# Protoboard_MX2-8-7-ESP12.net
KiCad netlist of a schematic drawn in EAGLE
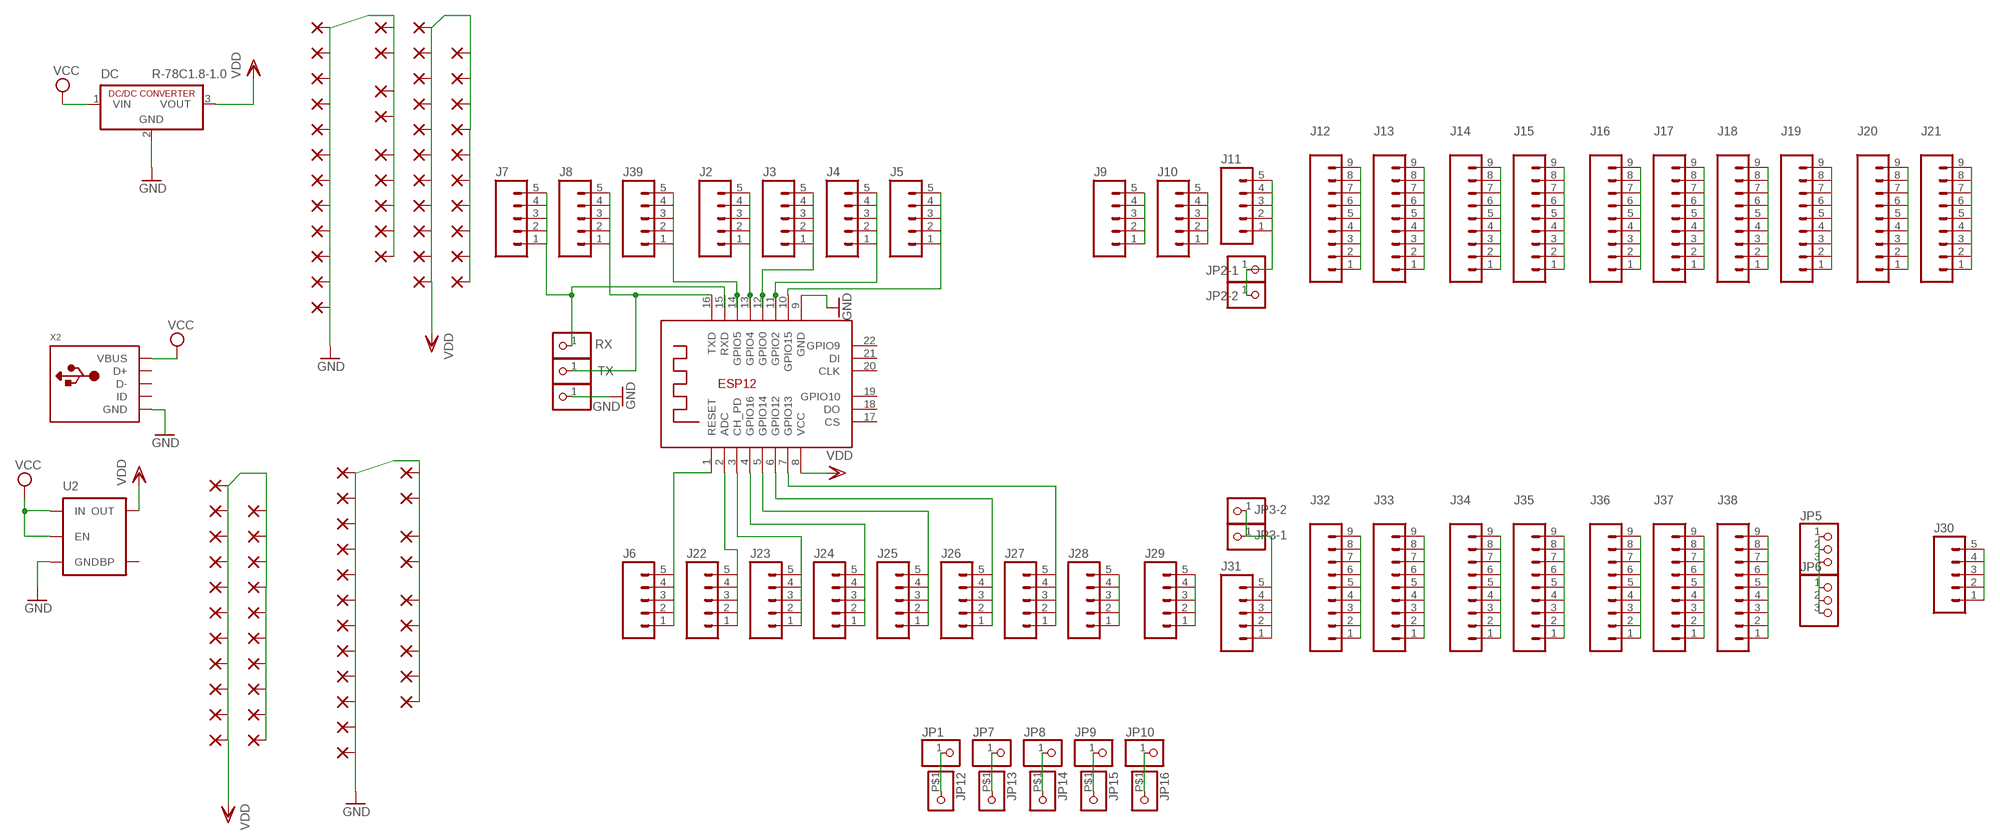
[diagram p0: schematic, sheet 1]

(export (version "E")
  (design (tool "Eeschema 10.0.6"))
  (components
    (comp (ref "DC")
      (value "R-78C1.8-1.0")
      (footprint "eagle-import:SIP3")
      (libsource (lib "eagle-import") (part "R-78C-1.01.8"))
    )
    (comp (ref "GND")
      (value "PINHD-1X1CB")
      (footprint "eagle-import:1X01-CLEANBIG")
      (libsource (lib "eagle-import") (part "PINHD-1X1CB"))
    )
    (comp (ref "J2")
      (value "M05NO_SILK")
      (footprint "eagle-import:1X05_NO_SILK")
      (libsource (lib "eagle-import") (part "M05NO_SILK"))
    )
    (comp (ref "J3")
      (value "M05NO_SILK")
      (footprint "eagle-import:1X05_NO_SILK")
      (libsource (lib "eagle-import") (part "M05NO_SILK"))
    )
    (comp (ref "J4")
      (value "M05NO_SILK")
      (footprint "eagle-import:1X05_NO_SILK")
      (libsource (lib "eagle-import") (part "M05NO_SILK"))
    )
    (comp (ref "J5")
      (value "M05NO_SILK")
      (footprint "eagle-import:1X05_NO_SILK")
      (libsource (lib "eagle-import") (part "M05NO_SILK"))
    )
    (comp (ref "J6")
      (value "M05NO_SILK")
      (footprint "eagle-import:1X05_NO_SILK")
      (libsource (lib "eagle-import") (part "M05NO_SILK"))
    )
    (comp (ref "J7")
      (value "M05NO_SILK")
      (footprint "eagle-import:1X05_NO_SILK")
      (libsource (lib "eagle-import") (part "M05NO_SILK"))
    )
    (comp (ref "J8")
      (value "M05NO_SILK")
      (footprint "eagle-import:1X05_NO_SILK")
      (libsource (lib "eagle-import") (part "M05NO_SILK"))
    )
    (comp (ref "J9")
      (value "M05NO_SILK")
      (footprint "eagle-import:1X05_NO_SILK")
      (libsource (lib "eagle-import") (part "M05NO_SILK"))
    )
    (comp (ref "J10")
      (value "M05NO_SILK")
      (footprint "eagle-import:1X05_NO_SILK")
      (libsource (lib "eagle-import") (part "M05NO_SILK"))
    )
    (comp (ref "J11")
      (value "M05NO_SILK")
      (footprint "eagle-import:1X05_NO_SILK")
      (libsource (lib "eagle-import") (part "M05NO_SILK"))
    )
    (comp (ref "J12")
      (value "M09NO_SILK")
      (footprint "eagle-import:1X09_NO_SILK")
      (libsource (lib "eagle-import") (part "M09NO_SILK"))
    )
    (comp (ref "J13")
      (value "M09NO_SILK")
      (footprint "eagle-import:1X09_NO_SILK")
      (libsource (lib "eagle-import") (part "M09NO_SILK"))
    )
    (comp (ref "J14")
      (value "M09NO_SILK")
      (footprint "eagle-import:1X09_NO_SILK")
      (libsource (lib "eagle-import") (part "M09NO_SILK"))
    )
    (comp (ref "J15")
      (value "M09NO_SILK")
      (footprint "eagle-import:1X09_NO_SILK")
      (libsource (lib "eagle-import") (part "M09NO_SILK"))
    )
    (comp (ref "J16")
      (value "M09NO_SILK")
      (footprint "eagle-import:1X09_NO_SILK")
      (libsource (lib "eagle-import") (part "M09NO_SILK"))
    )
    (comp (ref "J17")
      (value "M09NO_SILK")
      (footprint "eagle-import:1X09_NO_SILK")
      (libsource (lib "eagle-import") (part "M09NO_SILK"))
    )
    (comp (ref "J18")
      (value "M09NO_SILK")
      (footprint "eagle-import:1X09_NO_SILK")
      (libsource (lib "eagle-import") (part "M09NO_SILK"))
    )
    (comp (ref "J19")
      (value "M09NO_SILK")
      (footprint "eagle-import:1X09_NO_SILK")
      (libsource (lib "eagle-import") (part "M09NO_SILK"))
    )
    (comp (ref "J20")
      (value "M09NO_SILK")
      (footprint "eagle-import:1X09_NO_SILK")
      (libsource (lib "eagle-import") (part "M09NO_SILK"))
    )
    (comp (ref "J21")
      (value "M09NO_SILK")
      (footprint "eagle-import:1X09_NO_SILK")
      (libsource (lib "eagle-import") (part "M09NO_SILK"))
    )
    (comp (ref "J22")
      (value "M05NO_SILK")
      (footprint "eagle-import:1X05_NO_SILK")
      (libsource (lib "eagle-import") (part "M05NO_SILK"))
    )
    (comp (ref "J23")
      (value "M05NO_SILK")
      (footprint "eagle-import:1X05_NO_SILK")
      (libsource (lib "eagle-import") (part "M05NO_SILK"))
    )
    (comp (ref "J24")
      (value "M05NO_SILK")
      (footprint "eagle-import:1X05_NO_SILK")
      (libsource (lib "eagle-import") (part "M05NO_SILK"))
    )
    (comp (ref "J25")
      (value "M05NO_SILK")
      (footprint "eagle-import:1X05_NO_SILK")
      (libsource (lib "eagle-import") (part "M05NO_SILK"))
    )
    (comp (ref "J26")
      (value "M05NO_SILK")
      (footprint "eagle-import:1X05_NO_SILK")
      (libsource (lib "eagle-import") (part "M05NO_SILK"))
    )
    (comp (ref "J27")
      (value "M05NO_SILK")
      (footprint "eagle-import:1X05_NO_SILK")
      (libsource (lib "eagle-import") (part "M05NO_SILK"))
    )
    (comp (ref "J28")
      (value "M05NO_SILK")
      (footprint "eagle-import:1X05_NO_SILK")
      (libsource (lib "eagle-import") (part "M05NO_SILK"))
    )
    (comp (ref "J29")
      (value "M05NO_SILK")
      (footprint "eagle-import:1X05_NO_SILK")
      (libsource (lib "eagle-import") (part "M05NO_SILK"))
    )
    (comp (ref "J30")
      (value "M05NO_SILK")
      (footprint "eagle-import:1X05_NO_SILK")
      (libsource (lib "eagle-import") (part "M05NO_SILK"))
    )
    (comp (ref "J31")
      (value "M05NO_SILK")
      (footprint "eagle-import:1X05_NO_SILK")
      (libsource (lib "eagle-import") (part "M05NO_SILK"))
    )
    (comp (ref "J32")
      (value "M09NO_SILK")
      (footprint "eagle-import:1X09_NO_SILK")
      (libsource (lib "eagle-import") (part "M09NO_SILK"))
    )
    (comp (ref "J33")
      (value "M09NO_SILK")
      (footprint "eagle-import:1X09_NO_SILK")
      (libsource (lib "eagle-import") (part "M09NO_SILK"))
    )
    (comp (ref "J34")
      (value "M09NO_SILK")
      (footprint "eagle-import:1X09_NO_SILK")
      (libsource (lib "eagle-import") (part "M09NO_SILK"))
    )
    (comp (ref "J35")
      (value "M09NO_SILK")
      (footprint "eagle-import:1X09_NO_SILK")
      (libsource (lib "eagle-import") (part "M09NO_SILK"))
    )
    (comp (ref "J36")
      (value "M09NO_SILK")
      (footprint "eagle-import:1X09_NO_SILK")
      (libsource (lib "eagle-import") (part "M09NO_SILK"))
    )
    (comp (ref "J37")
      (value "M09NO_SILK")
      (footprint "eagle-import:1X09_NO_SILK")
      (libsource (lib "eagle-import") (part "M09NO_SILK"))
    )
    (comp (ref "J38")
      (value "M09NO_SILK")
      (footprint "eagle-import:1X09_NO_SILK")
      (libsource (lib "eagle-import") (part "M09NO_SILK"))
    )
    (comp (ref "J39")
      (value "M05NO_SILK")
      (footprint "eagle-import:1X05_NO_SILK")
      (libsource (lib "eagle-import") (part "M05NO_SILK"))
    )
    (comp (ref "JP1")
      (value "PINHD-1X1CB")
      (footprint "eagle-import:1X01-CLEANBIG")
      (libsource (lib "eagle-import") (part "PINHD-1X1CB"))
    )
    (comp (ref "JP2-1")
      (value "PINHD-1X1CB")
      (footprint "eagle-import:1X01-CLEANBIG")
      (libsource (lib "eagle-import") (part "PINHD-1X1CB"))
    )
    (comp (ref "JP2-2")
      (value "PINHD-1X1CB")
      (footprint "eagle-import:1X01-CLEANBIG")
      (libsource (lib "eagle-import") (part "PINHD-1X1CB"))
    )
    (comp (ref "JP3-1")
      (value "PINHD-1X1CB")
      (footprint "eagle-import:1X01-CLEANBIG")
      (libsource (lib "eagle-import") (part "PINHD-1X1CB"))
    )
    (comp (ref "JP3-2")
      (value "PINHD-1X1CB")
      (footprint "eagle-import:1X01-CLEANBIG")
      (libsource (lib "eagle-import") (part "PINHD-1X1CB"))
    )
    (comp (ref "JP5")
      (value "PINHD-1X3CB")
      (footprint "eagle-import:1X03-CLEANBIG")
      (libsource (lib "eagle-import") (part "PINHD-1X3CB"))
    )
    (comp (ref "JP6")
      (value "PINHD-1X3CB")
      (footprint "eagle-import:1X03-CLEANBIG")
      (libsource (lib "eagle-import") (part "PINHD-1X3CB"))
    )
    (comp (ref "JP7")
      (value "PINHD-1X1CB")
      (footprint "eagle-import:1X01-CLEANBIG")
      (libsource (lib "eagle-import") (part "PINHD-1X1CB"))
    )
    (comp (ref "JP8")
      (value "PINHD-1X1CB")
      (footprint "eagle-import:1X01-CLEANBIG")
      (libsource (lib "eagle-import") (part "PINHD-1X1CB"))
    )
    (comp (ref "JP9")
      (value "PINHD-1X1CB")
      (footprint "eagle-import:1X01-CLEANBIG")
      (libsource (lib "eagle-import") (part "PINHD-1X1CB"))
    )
    (comp (ref "JP10")
      (value "PINHD-1X1CB")
      (footprint "eagle-import:1X01-CLEANBIG")
      (libsource (lib "eagle-import") (part "PINHD-1X1CB"))
    )
    (comp (ref "JP12")
      (value "PINHD-1X1-BIGPOGO")
      (footprint "eagle-import:1X1-BIGPOGO")
      (libsource (lib "eagle-import") (part "PINHD-1X1-BIGPOGO"))
    )
    (comp (ref "JP13")
      (value "PINHD-1X1-BIGPOGO")
      (footprint "eagle-import:1X1-BIGPOGO")
      (libsource (lib "eagle-import") (part "PINHD-1X1-BIGPOGO"))
    )
    (comp (ref "JP14")
      (value "PINHD-1X1-BIGPOGO")
      (footprint "eagle-import:1X1-BIGPOGO")
      (libsource (lib "eagle-import") (part "PINHD-1X1-BIGPOGO"))
    )
    (comp (ref "JP15")
      (value "PINHD-1X1-BIGPOGO")
      (footprint "eagle-import:1X1-BIGPOGO")
      (libsource (lib "eagle-import") (part "PINHD-1X1-BIGPOGO"))
    )
    (comp (ref "JP16")
      (value "PINHD-1X1-BIGPOGO")
      (footprint "eagle-import:1X1-BIGPOGO")
      (libsource (lib "eagle-import") (part "PINHD-1X1-BIGPOGO"))
    )
    (comp (ref "PAD1")
      (value "1,6/0,8")
      (footprint "eagle-import:1,6_0,8")
      (libsource (lib "eagle-import") (part "1,6/0,8"))
    )
    (comp (ref "PAD2")
      (value "1,6/0,8")
      (footprint "eagle-import:1,6_0,8")
      (libsource (lib "eagle-import") (part "1,6/0,8"))
    )
    (comp (ref "PAD3")
      (value "1,6/0,8")
      (footprint "eagle-import:1,6_0,8")
      (libsource (lib "eagle-import") (part "1,6/0,8"))
    )
    (comp (ref "PAD4")
      (value "1,6/0,8")
      (footprint "eagle-import:1,6_0,8")
      (libsource (lib "eagle-import") (part "1,6/0,8"))
    )
    (comp (ref "PAD5")
      (value "1,6/0,8")
      (footprint "eagle-import:1,6_0,8")
      (libsource (lib "eagle-import") (part "1,6/0,8"))
    )
    (comp (ref "PAD6")
      (value "1,6/0,8")
      (footprint "eagle-import:1,6_0,8")
      (libsource (lib "eagle-import") (part "1,6/0,8"))
    )
    (comp (ref "PAD7")
      (value "1,6/0,8")
      (footprint "eagle-import:1,6_0,8")
      (libsource (lib "eagle-import") (part "1,6/0,8"))
    )
    (comp (ref "PAD8")
      (value "1,6/0,8")
      (footprint "eagle-import:1,6_0,8")
      (libsource (lib "eagle-import") (part "1,6/0,8"))
    )
    (comp (ref "PAD9")
      (value "1,6/0,8")
      (footprint "eagle-import:1,6_0,8")
      (libsource (lib "eagle-import") (part "1,6/0,8"))
    )
    (comp (ref "PAD10")
      (value "1,6/0,8")
      (footprint "eagle-import:1,6_0,8")
      (libsource (lib "eagle-import") (part "1,6/0,8"))
    )
    (comp (ref "PAD11")
      (value "1,6/0,8")
      (footprint "eagle-import:1,6_0,8")
      (libsource (lib "eagle-import") (part "1,6/0,8"))
    )
    (comp (ref "PAD12")
      (value "1,6/0,8")
      (footprint "eagle-import:1,6_0,8")
      (libsource (lib "eagle-import") (part "1,6/0,8"))
    )
    (comp (ref "PAD13")
      (value "1,6/0,8")
      (footprint "eagle-import:1,6_0,8")
      (libsource (lib "eagle-import") (part "1,6/0,8"))
    )
    (comp (ref "PAD14")
      (value "1,6/0,8")
      (footprint "eagle-import:1,6_0,8")
      (libsource (lib "eagle-import") (part "1,6/0,8"))
    )
    (comp (ref "PAD15")
      (value "1,6/0,8")
      (footprint "eagle-import:1,6_0,8")
      (libsource (lib "eagle-import") (part "1,6/0,8"))
    )
    (comp (ref "PAD16")
      (value "1,6/0,8")
      (footprint "eagle-import:1,6_0,8")
      (libsource (lib "eagle-import") (part "1,6/0,8"))
    )
    (comp (ref "PAD17")
      (value "1,6/0,8")
      (footprint "eagle-import:1,6_0,8")
      (libsource (lib "eagle-import") (part "1,6/0,8"))
    )
    (comp (ref "PAD18")
      (value "1,6/0,8")
      (footprint "eagle-import:1,6_0,8")
      (libsource (lib "eagle-import") (part "1,6/0,8"))
    )
    (comp (ref "PAD19")
      (value "1,6/0,8")
      (footprint "eagle-import:1,6_0,8")
      (libsource (lib "eagle-import") (part "1,6/0,8"))
    )
    (comp (ref "PAD22")
      (value "1,6/0,8")
      (footprint "eagle-import:1,6_0,8")
      (libsource (lib "eagle-import") (part "1,6/0,8"))
    )
    (comp (ref "PAD23")
      (value "1,6/0,8")
      (footprint "eagle-import:1,6_0,8")
      (libsource (lib "eagle-import") (part "1,6/0,8"))
    )
    (comp (ref "PAD24")
      (value "1,6/0,8")
      (footprint "eagle-import:1,6_0,8")
      (libsource (lib "eagle-import") (part "1,6/0,8"))
    )
    (comp (ref "PAD25")
      (value "1,6/0,8")
      (footprint "eagle-import:1,6_0,8")
      (libsource (lib "eagle-import") (part "1,6/0,8"))
    )
    (comp (ref "PAD26")
      (value "1,6/0,8")
      (footprint "eagle-import:1,6_0,8")
      (libsource (lib "eagle-import") (part "1,6/0,8"))
    )
    (comp (ref "PAD27")
      (value "1,6/0,8")
      (footprint "eagle-import:1,6_0,8")
      (libsource (lib "eagle-import") (part "1,6/0,8"))
    )
    (comp (ref "PAD28")
      (value "1,6/0,8")
      (footprint "eagle-import:1,6_0,8")
      (libsource (lib "eagle-import") (part "1,6/0,8"))
    )
    (comp (ref "PAD29")
      (value "1,6/0,8")
      (footprint "eagle-import:1,6_0,8")
      (libsource (lib "eagle-import") (part "1,6/0,8"))
    )
    (comp (ref "PAD30")
      (value "1,6/0,8")
      (footprint "eagle-import:1,6_0,8")
      (libsource (lib "eagle-import") (part "1,6/0,8"))
    )
    (comp (ref "PAD31")
      (value "1,6/0,8")
      (footprint "eagle-import:1,6_0,8")
      (libsource (lib "eagle-import") (part "1,6/0,8"))
    )
    (comp (ref "PAD32")
      (value "1,6/0,8")
      (footprint "eagle-import:1,6_0,8")
      (libsource (lib "eagle-import") (part "1,6/0,8"))
    )
    (comp (ref "PAD33")
      (value "1,6/0,8")
      (footprint "eagle-import:1,6_0,8")
      (libsource (lib "eagle-import") (part "1,6/0,8"))
    )
    (comp (ref "PAD34")
      (value "1,6/0,8")
      (footprint "eagle-import:1,6_0,8")
      (libsource (lib "eagle-import") (part "1,6/0,8"))
    )
    (comp (ref "PAD35")
      (value "1,6/0,8")
      (footprint "eagle-import:1,6_0,8")
      (libsource (lib "eagle-import") (part "1,6/0,8"))
    )
    (comp (ref "PAD36")
      (value "1,6/0,8")
      (footprint "eagle-import:1,6_0,8")
      (libsource (lib "eagle-import") (part "1,6/0,8"))
    )
    (comp (ref "PAD37")
      (value "1,6/0,8")
      (footprint "eagle-import:1,6_0,8")
      (libsource (lib "eagle-import") (part "1,6/0,8"))
    )
    (comp (ref "PAD39")
      (value "1,6/0,8")
      (footprint "eagle-import:1,6_0,8")
      (libsource (lib "eagle-import") (part "1,6/0,8"))
    )
    (comp (ref "PAD40")
      (value "1,6/0,8")
      (footprint "eagle-import:1,6_0,8")
      (libsource (lib "eagle-import") (part "1,6/0,8"))
    )
    (comp (ref "PAD41")
      (value "1,6/0,8")
      (footprint "eagle-import:1,6_0,8")
      (libsource (lib "eagle-import") (part "1,6/0,8"))
    )
    (comp (ref "PAD43")
      (value "1,6/0,8")
      (footprint "eagle-import:1,6_0,8")
      (libsource (lib "eagle-import") (part "1,6/0,8"))
    )
    (comp (ref "PAD44")
      (value "1,6/0,8")
      (footprint "eagle-import:1,6_0,8")
      (libsource (lib "eagle-import") (part "1,6/0,8"))
    )
    (comp (ref "PAD45")
      (value "1,6/0,8")
      (footprint "eagle-import:1,6_0,8")
      (libsource (lib "eagle-import") (part "1,6/0,8"))
    )
    (comp (ref "PAD46")
      (value "1,6/0,8")
      (footprint "eagle-import:1,6_0,8")
      (libsource (lib "eagle-import") (part "1,6/0,8"))
    )
    (comp (ref "PAD421")
      (value "1,6/0,8")
      (footprint "eagle-import:1,6_0,8")
      (libsource (lib "eagle-import") (part "1,6/0,8"))
    )
    (comp (ref "PAD422")
      (value "1,6/0,8")
      (footprint "eagle-import:1,6_0,8")
      (libsource (lib "eagle-import") (part "1,6/0,8"))
    )
    (comp (ref "PAD423")
      (value "1,6/0,8")
      (footprint "eagle-import:1,6_0,8")
      (libsource (lib "eagle-import") (part "1,6/0,8"))
    )
    (comp (ref "PAD424")
      (value "1,6/0,8")
      (footprint "eagle-import:1,6_0,8")
      (libsource (lib "eagle-import") (part "1,6/0,8"))
    )
    (comp (ref "PAD425")
      (value "1,6/0,8")
      (footprint "eagle-import:1,6_0,8")
      (libsource (lib "eagle-import") (part "1,6/0,8"))
    )
    (comp (ref "PAD426")
      (value "1,6/0,8")
      (footprint "eagle-import:1,6_0,8")
      (libsource (lib "eagle-import") (part "1,6/0,8"))
    )
    (comp (ref "PAD427")
      (value "1,6/0,8")
      (footprint "eagle-import:1,6_0,8")
      (libsource (lib "eagle-import") (part "1,6/0,8"))
    )
    (comp (ref "PAD428")
      (value "1,6/0,8")
      (footprint "eagle-import:1,6_0,8")
      (libsource (lib "eagle-import") (part "1,6/0,8"))
    )
    (comp (ref "PAD429")
      (value "1,6/0,8")
      (footprint "eagle-import:1,6_0,8")
      (libsource (lib "eagle-import") (part "1,6/0,8"))
    )
    (comp (ref "PAD430")
      (value "1,6/0,8")
      (footprint "eagle-import:1,6_0,8")
      (libsource (lib "eagle-import") (part "1,6/0,8"))
    )
    (comp (ref "PAD431")
      (value "1,6/0,8")
      (footprint "eagle-import:1,6_0,8")
      (libsource (lib "eagle-import") (part "1,6/0,8"))
    )
    (comp (ref "PAD432")
      (value "1,6/0,8")
      (footprint "eagle-import:1,6_0,8")
      (libsource (lib "eagle-import") (part "1,6/0,8"))
    )
    (comp (ref "PAD433")
      (value "1,6/0,8")
      (footprint "eagle-import:1,6_0,8")
      (libsource (lib "eagle-import") (part "1,6/0,8"))
    )
    (comp (ref "PAD434")
      (value "1,6/0,8")
      (footprint "eagle-import:1,6_0,8")
      (libsource (lib "eagle-import") (part "1,6/0,8"))
    )
    (comp (ref "PAD435")
      (value "1,6/0,8")
      (footprint "eagle-import:1,6_0,8")
      (libsource (lib "eagle-import") (part "1,6/0,8"))
    )
    (comp (ref "PAD436")
      (value "1,6/0,8")
      (footprint "eagle-import:1,6_0,8")
      (libsource (lib "eagle-import") (part "1,6/0,8"))
    )
    (comp (ref "PAD437")
      (value "1,6/0,8")
      (footprint "eagle-import:1,6_0,8")
      (libsource (lib "eagle-import") (part "1,6/0,8"))
    )
    (comp (ref "PAD438")
      (value "1,6/0,8")
      (footprint "eagle-import:1,6_0,8")
      (libsource (lib "eagle-import") (part "1,6/0,8"))
    )
    (comp (ref "PAD439")
      (value "1,6/0,8")
      (footprint "eagle-import:1,6_0,8")
      (libsource (lib "eagle-import") (part "1,6/0,8"))
    )
    (comp (ref "PAD440")
      (value "1,6/0,8")
      (footprint "eagle-import:1,6_0,8")
      (libsource (lib "eagle-import") (part "1,6/0,8"))
    )
    (comp (ref "PAD441")
      (value "1,6/0,8")
      (footprint "eagle-import:1,6_0,8")
      (libsource (lib "eagle-import") (part "1,6/0,8"))
    )
    (comp (ref "PAD442")
      (value "1,6/0,8")
      (footprint "eagle-import:1,6_0,8")
      (libsource (lib "eagle-import") (part "1,6/0,8"))
    )
    (comp (ref "PAD443")
      (value "1,6/0,8")
      (footprint "eagle-import:1,6_0,8")
      (libsource (lib "eagle-import") (part "1,6/0,8"))
    )
    (comp (ref "PAD444")
      (value "1,6/0,8")
      (footprint "eagle-import:1,6_0,8")
      (libsource (lib "eagle-import") (part "1,6/0,8"))
    )
    (comp (ref "PAD445")
      (value "1,6/0,8")
      (footprint "eagle-import:1,6_0,8")
      (libsource (lib "eagle-import") (part "1,6/0,8"))
    )
    (comp (ref "PAD446")
      (value "1,6/0,8")
      (footprint "eagle-import:1,6_0,8")
      (libsource (lib "eagle-import") (part "1,6/0,8"))
    )
    (comp (ref "PAD447")
      (value "1,6/0,8")
      (footprint "eagle-import:1,6_0,8")
      (libsource (lib "eagle-import") (part "1,6/0,8"))
    )
    (comp (ref "PAD448")
      (value "1,6/0,8")
      (footprint "eagle-import:1,6_0,8")
      (libsource (lib "eagle-import") (part "1,6/0,8"))
    )
    (comp (ref "PAD449")
      (value "1,6/0,8")
      (footprint "eagle-import:1,6_0,8")
      (libsource (lib "eagle-import") (part "1,6/0,8"))
    )
    (comp (ref "PAD450")
      (value "1,6/0,8")
      (footprint "eagle-import:1,6_0,8")
      (libsource (lib "eagle-import") (part "1,6/0,8"))
    )
    (comp (ref "PAD451")
      (value "1,6/0,8")
      (footprint "eagle-import:1,6_0,8")
      (libsource (lib "eagle-import") (part "1,6/0,8"))
    )
    (comp (ref "PAD452")
      (value "1,6/0,8")
      (footprint "eagle-import:1,6_0,8")
      (libsource (lib "eagle-import") (part "1,6/0,8"))
    )
    (comp (ref "PAD453")
      (value "1,6/0,8")
      (footprint "eagle-import:1,6_0,8")
      (libsource (lib "eagle-import") (part "1,6/0,8"))
    )
    (comp (ref "PAD454")
      (value "1,6/0,8")
      (footprint "eagle-import:1,6_0,8")
      (libsource (lib "eagle-import") (part "1,6/0,8"))
    )
    (comp (ref "PAD455")
      (value "1,6/0,8")
      (footprint "eagle-import:1,6_0,8")
      (libsource (lib "eagle-import") (part "1,6/0,8"))
    )
    (comp (ref "PAD456")
      (value "1,6/0,8")
      (footprint "eagle-import:1,6_0,8")
      (libsource (lib "eagle-import") (part "1,6/0,8"))
    )
    (comp (ref "PAD457")
      (value "1,6/0,8")
      (footprint "eagle-import:1,6_0,8")
      (libsource (lib "eagle-import") (part "1,6/0,8"))
    )
    (comp (ref "PAD458")
      (value "1,6/0,8")
      (footprint "eagle-import:1,6_0,8")
      (libsource (lib "eagle-import") (part "1,6/0,8"))
    )
    (comp (ref "PAD459")
      (value "1,6/0,8")
      (footprint "eagle-import:1,6_0,8")
      (libsource (lib "eagle-import") (part "1,6/0,8"))
    )
    (comp (ref "PAD460")
      (value "1,6/0,8")
      (footprint "eagle-import:1,6_0,8")
      (libsource (lib "eagle-import") (part "1,6/0,8"))
    )
    (comp (ref "PAD461")
      (value "1,6/0,8")
      (footprint "eagle-import:1,6_0,8")
      (libsource (lib "eagle-import") (part "1,6/0,8"))
    )
    (comp (ref "PAD462")
      (value "1,6/0,8")
      (footprint "eagle-import:1,6_0,8")
      (libsource (lib "eagle-import") (part "1,6/0,8"))
    )
    (comp (ref "RX")
      (value "PINHD-1X1CB")
      (footprint "eagle-import:1X01-CLEANBIG")
      (libsource (lib "eagle-import") (part "PINHD-1X1CB"))
    )
    (comp (ref "TX")
      (value "PINHD-1X1CB")
      (footprint "eagle-import:1X01-CLEANBIG")
      (libsource (lib "eagle-import") (part "PINHD-1X1CB"))
    )
    (comp (ref "U2")
      (value "MIC52053.3V")
      (footprint "eagle-import:SOT23-5")
      (libsource (lib "eagle-import") (part "MIC52053.3V"))
    )
    (comp (ref "X1")
      (value "ESP-12E")
      (footprint "eagle-import:ESP-12E")
      (libsource (lib "eagle-import") (part "ESP-12E"))
    )
    (comp (ref "X2")
      (value "USB_MICRO_20329_V2")
      (footprint "eagle-import:4UCONN_20329_V2")
      (libsource (lib "eagle-import") (part "USB_MICRO_20329_V2"))
    )
  )
  (nets
    (net (code "1") (name "GND") (class "Default")
      (node (ref "DC") (pin "2") (pinfunction "GND_2") (pintype "passive"))
      (node (ref "GND") (pin "1") (pinfunction "1_1") (pintype "passive"))
      (node (ref "PAD1") (pin "1") (pinfunction "P_1") (pintype "passive"))
      (node (ref "PAD10") (pin "1") (pinfunction "P_1") (pintype "passive"))
      (node (ref "PAD11") (pin "1") (pinfunction "P_1") (pintype "passive"))
      (node (ref "PAD12") (pin "1") (pinfunction "P_1") (pintype "passive"))
      (node (ref "PAD13") (pin "1") (pinfunction "P_1") (pintype "passive"))
      (node (ref "PAD14") (pin "1") (pinfunction "P_1") (pintype "passive"))
      (node (ref "PAD16") (pin "1") (pinfunction "P_1") (pintype "passive"))
      (node (ref "PAD17") (pin "1") (pinfunction "P_1") (pintype "passive"))
      (node (ref "PAD18") (pin "1") (pinfunction "P_1") (pintype "passive"))
      (node (ref "PAD19") (pin "1") (pinfunction "P_1") (pintype "passive"))
      (node (ref "PAD2") (pin "1") (pinfunction "P_1") (pintype "passive"))
      (node (ref "PAD22") (pin "1") (pinfunction "P_1") (pintype "passive"))
      (node (ref "PAD23") (pin "1") (pinfunction "P_1") (pintype "passive"))
      (node (ref "PAD24") (pin "1") (pinfunction "P_1") (pintype "passive"))
      (node (ref "PAD3") (pin "1") (pinfunction "P_1") (pintype "passive"))
      (node (ref "PAD4") (pin "1") (pinfunction "P_1") (pintype "passive"))
      (node (ref "PAD421") (pin "1") (pinfunction "P_1") (pintype "passive"))
      (node (ref "PAD422") (pin "1") (pinfunction "P_1") (pintype "passive"))
      (node (ref "PAD423") (pin "1") (pinfunction "P_1") (pintype "passive"))
      (node (ref "PAD424") (pin "1") (pinfunction "P_1") (pintype "passive"))
      (node (ref "PAD425") (pin "1") (pinfunction "P_1") (pintype "passive"))
      (node (ref "PAD426") (pin "1") (pinfunction "P_1") (pintype "passive"))
      (node (ref "PAD427") (pin "1") (pinfunction "P_1") (pintype "passive"))
      (node (ref "PAD428") (pin "1") (pinfunction "P_1") (pintype "passive"))
      (node (ref "PAD429") (pin "1") (pinfunction "P_1") (pintype "passive"))
      (node (ref "PAD430") (pin "1") (pinfunction "P_1") (pintype "passive"))
      (node (ref "PAD431") (pin "1") (pinfunction "P_1") (pintype "passive"))
      (node (ref "PAD432") (pin "1") (pinfunction "P_1") (pintype "passive"))
      (node (ref "PAD433") (pin "1") (pinfunction "P_1") (pintype "passive"))
      (node (ref "PAD434") (pin "1") (pinfunction "P_1") (pintype "passive"))
      (node (ref "PAD435") (pin "1") (pinfunction "P_1") (pintype "passive"))
      (node (ref "PAD436") (pin "1") (pinfunction "P_1") (pintype "passive"))
      (node (ref "PAD437") (pin "1") (pinfunction "P_1") (pintype "passive"))
      (node (ref "PAD438") (pin "1") (pinfunction "P_1") (pintype "passive"))
      (node (ref "PAD439") (pin "1") (pinfunction "P_1") (pintype "passive"))
      (node (ref "PAD440") (pin "1") (pinfunction "P_1") (pintype "passive"))
      (node (ref "PAD441") (pin "1") (pinfunction "P_1") (pintype "passive"))
      (node (ref "PAD5") (pin "1") (pinfunction "P_1") (pintype "passive"))
      (node (ref "PAD6") (pin "1") (pinfunction "P_1") (pintype "passive"))
      (node (ref "PAD7") (pin "1") (pinfunction "P_1") (pintype "passive"))
      (node (ref "PAD8") (pin "1") (pinfunction "P_1") (pintype "passive"))
      (node (ref "PAD9") (pin "1") (pinfunction "P_1") (pintype "passive"))
      (node (ref "U2") (pin "2") (pinfunction "GND_2") (pintype "input"))
      (node (ref "X1") (pin "9") (pinfunction "GND_9") (pintype "power_in"))
    )
    (net (code "2") (name "Net-(J9-Pad1)") (class "Default")
      (node (ref "J9") (pin "1") (pinfunction "1_1") (pintype "passive"))
      (node (ref "J9") (pin "2") (pinfunction "2_2") (pintype "passive"))
      (node (ref "J9") (pin "3") (pinfunction "3_3") (pintype "passive"))
      (node (ref "J9") (pin "4") (pinfunction "4_4") (pintype "passive"))
      (node (ref "J9") (pin "5") (pinfunction "5_5") (pintype "passive"))
    )
    (net (code "3") (name "Net-(J10-Pad1)") (class "Default")
      (node (ref "J10") (pin "1") (pinfunction "1_1") (pintype "passive"))
      (node (ref "J10") (pin "2") (pinfunction "2_2") (pintype "passive"))
      (node (ref "J10") (pin "3") (pinfunction "3_3") (pintype "passive"))
      (node (ref "J10") (pin "4") (pinfunction "4_4") (pintype "passive"))
      (node (ref "J10") (pin "5") (pinfunction "5_5") (pintype "passive"))
    )
    (net (code "4") (name "Net-(J11-Pad1)") (class "Default")
      (node (ref "J11") (pin "1") (pinfunction "1_1") (pintype "passive"))
      (node (ref "J11") (pin "2") (pinfunction "2_2") (pintype "passive"))
      (node (ref "J11") (pin "3") (pinfunction "3_3") (pintype "passive"))
      (node (ref "J11") (pin "4") (pinfunction "4_4") (pintype "passive"))
      (node (ref "J11") (pin "5") (pinfunction "5_5") (pintype "passive"))
      (node (ref "JP2-1") (pin "1") (pinfunction "1_1") (pintype "passive"))
      (node (ref "JP2-2") (pin "1") (pinfunction "1_1") (pintype "passive"))
    )
    (net (code "5") (name "Net-(J12-Pad1)") (class "Default")
      (node (ref "J12") (pin "1") (pinfunction "1_1") (pintype "passive"))
      (node (ref "J12") (pin "2") (pinfunction "2_2") (pintype "passive"))
      (node (ref "J12") (pin "3") (pinfunction "3_3") (pintype "passive"))
      (node (ref "J12") (pin "4") (pinfunction "4_4") (pintype "passive"))
      (node (ref "J12") (pin "5") (pinfunction "5_5") (pintype "passive"))
      (node (ref "J12") (pin "6") (pinfunction "6_6") (pintype "passive"))
      (node (ref "J12") (pin "7") (pinfunction "7_7") (pintype "passive"))
      (node (ref "J12") (pin "8") (pinfunction "8_8") (pintype "passive"))
      (node (ref "J12") (pin "9") (pinfunction "9_9") (pintype "passive"))
    )
    (net (code "6") (name "Net-(J13-Pad1)") (class "Default")
      (node (ref "J13") (pin "1") (pinfunction "1_1") (pintype "passive"))
      (node (ref "J13") (pin "2") (pinfunction "2_2") (pintype "passive"))
      (node (ref "J13") (pin "3") (pinfunction "3_3") (pintype "passive"))
      (node (ref "J13") (pin "4") (pinfunction "4_4") (pintype "passive"))
      (node (ref "J13") (pin "5") (pinfunction "5_5") (pintype "passive"))
      (node (ref "J13") (pin "6") (pinfunction "6_6") (pintype "passive"))
      (node (ref "J13") (pin "7") (pinfunction "7_7") (pintype "passive"))
      (node (ref "J13") (pin "8") (pinfunction "8_8") (pintype "passive"))
      (node (ref "J13") (pin "9") (pinfunction "9_9") (pintype "passive"))
    )
    (net (code "7") (name "Net-(J14-Pad1)") (class "Default")
      (node (ref "J14") (pin "1") (pinfunction "1_1") (pintype "passive"))
      (node (ref "J14") (pin "2") (pinfunction "2_2") (pintype "passive"))
      (node (ref "J14") (pin "3") (pinfunction "3_3") (pintype "passive"))
      (node (ref "J14") (pin "4") (pinfunction "4_4") (pintype "passive"))
      (node (ref "J14") (pin "5") (pinfunction "5_5") (pintype "passive"))
      (node (ref "J14") (pin "6") (pinfunction "6_6") (pintype "passive"))
      (node (ref "J14") (pin "7") (pinfunction "7_7") (pintype "passive"))
      (node (ref "J14") (pin "8") (pinfunction "8_8") (pintype "passive"))
      (node (ref "J14") (pin "9") (pinfunction "9_9") (pintype "passive"))
    )
    (net (code "8") (name "Net-(J15-Pad1)") (class "Default")
      (node (ref "J15") (pin "1") (pinfunction "1_1") (pintype "passive"))
      (node (ref "J15") (pin "2") (pinfunction "2_2") (pintype "passive"))
      (node (ref "J15") (pin "3") (pinfunction "3_3") (pintype "passive"))
      (node (ref "J15") (pin "4") (pinfunction "4_4") (pintype "passive"))
      (node (ref "J15") (pin "5") (pinfunction "5_5") (pintype "passive"))
      (node (ref "J15") (pin "6") (pinfunction "6_6") (pintype "passive"))
      (node (ref "J15") (pin "7") (pinfunction "7_7") (pintype "passive"))
      (node (ref "J15") (pin "8") (pinfunction "8_8") (pintype "passive"))
      (node (ref "J15") (pin "9") (pinfunction "9_9") (pintype "passive"))
    )
    (net (code "9") (name "Net-(J16-Pad1)") (class "Default")
      (node (ref "J16") (pin "1") (pinfunction "1_1") (pintype "passive"))
      (node (ref "J16") (pin "2") (pinfunction "2_2") (pintype "passive"))
      (node (ref "J16") (pin "3") (pinfunction "3_3") (pintype "passive"))
      (node (ref "J16") (pin "4") (pinfunction "4_4") (pintype "passive"))
      (node (ref "J16") (pin "5") (pinfunction "5_5") (pintype "passive"))
      (node (ref "J16") (pin "6") (pinfunction "6_6") (pintype "passive"))
      (node (ref "J16") (pin "7") (pinfunction "7_7") (pintype "passive"))
      (node (ref "J16") (pin "8") (pinfunction "8_8") (pintype "passive"))
      (node (ref "J16") (pin "9") (pinfunction "9_9") (pintype "passive"))
    )
    (net (code "10") (name "Net-(J17-Pad1)") (class "Default")
      (node (ref "J17") (pin "1") (pinfunction "1_1") (pintype "passive"))
      (node (ref "J17") (pin "2") (pinfunction "2_2") (pintype "passive"))
      (node (ref "J17") (pin "3") (pinfunction "3_3") (pintype "passive"))
      (node (ref "J17") (pin "4") (pinfunction "4_4") (pintype "passive"))
      (node (ref "J17") (pin "5") (pinfunction "5_5") (pintype "passive"))
      (node (ref "J17") (pin "6") (pinfunction "6_6") (pintype "passive"))
      (node (ref "J17") (pin "7") (pinfunction "7_7") (pintype "passive"))
      (node (ref "J17") (pin "8") (pinfunction "8_8") (pintype "passive"))
      (node (ref "J17") (pin "9") (pinfunction "9_9") (pintype "passive"))
    )
    (net (code "11") (name "Net-(J18-Pad1)") (class "Default")
      (node (ref "J18") (pin "1") (pinfunction "1_1") (pintype "passive"))
      (node (ref "J18") (pin "2") (pinfunction "2_2") (pintype "passive"))
      (node (ref "J18") (pin "3") (pinfunction "3_3") (pintype "passive"))
      (node (ref "J18") (pin "4") (pinfunction "4_4") (pintype "passive"))
      (node (ref "J18") (pin "5") (pinfunction "5_5") (pintype "passive"))
      (node (ref "J18") (pin "6") (pinfunction "6_6") (pintype "passive"))
      (node (ref "J18") (pin "7") (pinfunction "7_7") (pintype "passive"))
      (node (ref "J18") (pin "8") (pinfunction "8_8") (pintype "passive"))
      (node (ref "J18") (pin "9") (pinfunction "9_9") (pintype "passive"))
    )
    (net (code "12") (name "Net-(J19-Pad1)") (class "Default")
      (node (ref "J19") (pin "1") (pinfunction "1_1") (pintype "passive"))
      (node (ref "J19") (pin "2") (pinfunction "2_2") (pintype "passive"))
      (node (ref "J19") (pin "3") (pinfunction "3_3") (pintype "passive"))
      (node (ref "J19") (pin "4") (pinfunction "4_4") (pintype "passive"))
      (node (ref "J19") (pin "5") (pinfunction "5_5") (pintype "passive"))
      (node (ref "J19") (pin "6") (pinfunction "6_6") (pintype "passive"))
      (node (ref "J19") (pin "7") (pinfunction "7_7") (pintype "passive"))
      (node (ref "J19") (pin "8") (pinfunction "8_8") (pintype "passive"))
      (node (ref "J19") (pin "9") (pinfunction "9_9") (pintype "passive"))
    )
    (net (code "13") (name "Net-(J20-Pad1)") (class "Default")
      (node (ref "J20") (pin "1") (pinfunction "1_1") (pintype "passive"))
      (node (ref "J20") (pin "2") (pinfunction "2_2") (pintype "passive"))
      (node (ref "J20") (pin "3") (pinfunction "3_3") (pintype "passive"))
      (node (ref "J20") (pin "4") (pinfunction "4_4") (pintype "passive"))
      (node (ref "J20") (pin "5") (pinfunction "5_5") (pintype "passive"))
      (node (ref "J20") (pin "6") (pinfunction "6_6") (pintype "passive"))
      (node (ref "J20") (pin "7") (pinfunction "7_7") (pintype "passive"))
      (node (ref "J20") (pin "8") (pinfunction "8_8") (pintype "passive"))
      (node (ref "J20") (pin "9") (pinfunction "9_9") (pintype "passive"))
    )
    (net (code "14") (name "Net-(J21-Pad1)") (class "Default")
      (node (ref "J21") (pin "1") (pinfunction "1_1") (pintype "passive"))
      (node (ref "J21") (pin "2") (pinfunction "2_2") (pintype "passive"))
      (node (ref "J21") (pin "3") (pinfunction "3_3") (pintype "passive"))
      (node (ref "J21") (pin "4") (pinfunction "4_4") (pintype "passive"))
      (node (ref "J21") (pin "5") (pinfunction "5_5") (pintype "passive"))
      (node (ref "J21") (pin "6") (pinfunction "6_6") (pintype "passive"))
      (node (ref "J21") (pin "7") (pinfunction "7_7") (pintype "passive"))
      (node (ref "J21") (pin "8") (pinfunction "8_8") (pintype "passive"))
      (node (ref "J21") (pin "9") (pinfunction "9_9") (pintype "passive"))
    )
    (net (code "15") (name "Net-(J28-Pad1)") (class "Default")
      (node (ref "J28") (pin "1") (pinfunction "1_1") (pintype "passive"))
      (node (ref "J28") (pin "2") (pinfunction "2_2") (pintype "passive"))
      (node (ref "J28") (pin "3") (pinfunction "3_3") (pintype "passive"))
      (node (ref "J28") (pin "4") (pinfunction "4_4") (pintype "passive"))
      (node (ref "J28") (pin "5") (pinfunction "5_5") (pintype "passive"))
    )
    (net (code "16") (name "Net-(J29-Pad1)") (class "Default")
      (node (ref "J29") (pin "1") (pinfunction "1_1") (pintype "passive"))
      (node (ref "J29") (pin "2") (pinfunction "2_2") (pintype "passive"))
      (node (ref "J29") (pin "3") (pinfunction "3_3") (pintype "passive"))
      (node (ref "J29") (pin "4") (pinfunction "4_4") (pintype "passive"))
      (node (ref "J29") (pin "5") (pinfunction "5_5") (pintype "passive"))
    )
    (net (code "17") (name "Net-(J30-Pad1)") (class "Default")
      (node (ref "J30") (pin "1") (pinfunction "1_1") (pintype "passive"))
      (node (ref "J30") (pin "2") (pinfunction "2_2") (pintype "passive"))
      (node (ref "J30") (pin "3") (pinfunction "3_3") (pintype "passive"))
      (node (ref "J30") (pin "4") (pinfunction "4_4") (pintype "passive"))
      (node (ref "J30") (pin "5") (pinfunction "5_5") (pintype "passive"))
    )
    (net (code "18") (name "Net-(J31-Pad1)") (class "Default")
      (node (ref "J31") (pin "1") (pinfunction "1_1") (pintype "passive"))
      (node (ref "J31") (pin "2") (pinfunction "2_2") (pintype "passive"))
      (node (ref "J31") (pin "3") (pinfunction "3_3") (pintype "passive"))
      (node (ref "J31") (pin "4") (pinfunction "4_4") (pintype "passive"))
      (node (ref "J31") (pin "5") (pinfunction "5_5") (pintype "passive"))
      (node (ref "JP3-1") (pin "1") (pinfunction "1_1") (pintype "passive"))
      (node (ref "JP3-2") (pin "1") (pinfunction "1_1") (pintype "passive"))
    )
    (net (code "19") (name "Net-(J32-Pad1)") (class "Default")
      (node (ref "J32") (pin "1") (pinfunction "1_1") (pintype "passive"))
      (node (ref "J32") (pin "2") (pinfunction "2_2") (pintype "passive"))
      (node (ref "J32") (pin "3") (pinfunction "3_3") (pintype "passive"))
      (node (ref "J32") (pin "4") (pinfunction "4_4") (pintype "passive"))
      (node (ref "J32") (pin "5") (pinfunction "5_5") (pintype "passive"))
      (node (ref "J32") (pin "6") (pinfunction "6_6") (pintype "passive"))
      (node (ref "J32") (pin "7") (pinfunction "7_7") (pintype "passive"))
      (node (ref "J32") (pin "8") (pinfunction "8_8") (pintype "passive"))
      (node (ref "J32") (pin "9") (pinfunction "9_9") (pintype "passive"))
    )
    (net (code "20") (name "Net-(J33-Pad1)") (class "Default")
      (node (ref "J33") (pin "1") (pinfunction "1_1") (pintype "passive"))
      (node (ref "J33") (pin "2") (pinfunction "2_2") (pintype "passive"))
      (node (ref "J33") (pin "3") (pinfunction "3_3") (pintype "passive"))
      (node (ref "J33") (pin "4") (pinfunction "4_4") (pintype "passive"))
      (node (ref "J33") (pin "5") (pinfunction "5_5") (pintype "passive"))
      (node (ref "J33") (pin "6") (pinfunction "6_6") (pintype "passive"))
      (node (ref "J33") (pin "7") (pinfunction "7_7") (pintype "passive"))
      (node (ref "J33") (pin "8") (pinfunction "8_8") (pintype "passive"))
      (node (ref "J33") (pin "9") (pinfunction "9_9") (pintype "passive"))
    )
    (net (code "21") (name "Net-(J34-Pad1)") (class "Default")
      (node (ref "J34") (pin "1") (pinfunction "1_1") (pintype "passive"))
      (node (ref "J34") (pin "2") (pinfunction "2_2") (pintype "passive"))
      (node (ref "J34") (pin "3") (pinfunction "3_3") (pintype "passive"))
      (node (ref "J34") (pin "4") (pinfunction "4_4") (pintype "passive"))
      (node (ref "J34") (pin "5") (pinfunction "5_5") (pintype "passive"))
      (node (ref "J34") (pin "6") (pinfunction "6_6") (pintype "passive"))
      (node (ref "J34") (pin "7") (pinfunction "7_7") (pintype "passive"))
      (node (ref "J34") (pin "8") (pinfunction "8_8") (pintype "passive"))
      (node (ref "J34") (pin "9") (pinfunction "9_9") (pintype "passive"))
    )
    (net (code "22") (name "Net-(J35-Pad1)") (class "Default")
      (node (ref "J35") (pin "1") (pinfunction "1_1") (pintype "passive"))
      (node (ref "J35") (pin "2") (pinfunction "2_2") (pintype "passive"))
      (node (ref "J35") (pin "3") (pinfunction "3_3") (pintype "passive"))
      (node (ref "J35") (pin "4") (pinfunction "4_4") (pintype "passive"))
      (node (ref "J35") (pin "5") (pinfunction "5_5") (pintype "passive"))
      (node (ref "J35") (pin "6") (pinfunction "6_6") (pintype "passive"))
      (node (ref "J35") (pin "7") (pinfunction "7_7") (pintype "passive"))
      (node (ref "J35") (pin "8") (pinfunction "8_8") (pintype "passive"))
      (node (ref "J35") (pin "9") (pinfunction "9_9") (pintype "passive"))
    )
    (net (code "23") (name "Net-(J36-Pad1)") (class "Default")
      (node (ref "J36") (pin "1") (pinfunction "1_1") (pintype "passive"))
      (node (ref "J36") (pin "2") (pinfunction "2_2") (pintype "passive"))
      (node (ref "J36") (pin "3") (pinfunction "3_3") (pintype "passive"))
      (node (ref "J36") (pin "4") (pinfunction "4_4") (pintype "passive"))
      (node (ref "J36") (pin "5") (pinfunction "5_5") (pintype "passive"))
      (node (ref "J36") (pin "6") (pinfunction "6_6") (pintype "passive"))
      (node (ref "J36") (pin "7") (pinfunction "7_7") (pintype "passive"))
      (node (ref "J36") (pin "8") (pinfunction "8_8") (pintype "passive"))
      (node (ref "J36") (pin "9") (pinfunction "9_9") (pintype "passive"))
    )
    (net (code "24") (name "Net-(J37-Pad1)") (class "Default")
      (node (ref "J37") (pin "1") (pinfunction "1_1") (pintype "passive"))
      (node (ref "J37") (pin "2") (pinfunction "2_2") (pintype "passive"))
      (node (ref "J37") (pin "3") (pinfunction "3_3") (pintype "passive"))
      (node (ref "J37") (pin "4") (pinfunction "4_4") (pintype "passive"))
      (node (ref "J37") (pin "5") (pinfunction "5_5") (pintype "passive"))
      (node (ref "J37") (pin "6") (pinfunction "6_6") (pintype "passive"))
      (node (ref "J37") (pin "7") (pinfunction "7_7") (pintype "passive"))
      (node (ref "J37") (pin "8") (pinfunction "8_8") (pintype "passive"))
      (node (ref "J37") (pin "9") (pinfunction "9_9") (pintype "passive"))
    )
    (net (code "25") (name "Net-(J38-Pad1)") (class "Default")
      (node (ref "J38") (pin "1") (pinfunction "1_1") (pintype "passive"))
      (node (ref "J38") (pin "2") (pinfunction "2_2") (pintype "passive"))
      (node (ref "J38") (pin "3") (pinfunction "3_3") (pintype "passive"))
      (node (ref "J38") (pin "4") (pinfunction "4_4") (pintype "passive"))
      (node (ref "J38") (pin "5") (pinfunction "5_5") (pintype "passive"))
      (node (ref "J38") (pin "6") (pinfunction "6_6") (pintype "passive"))
      (node (ref "J38") (pin "7") (pinfunction "7_7") (pintype "passive"))
      (node (ref "J38") (pin "8") (pinfunction "8_8") (pintype "passive"))
      (node (ref "J38") (pin "9") (pinfunction "9_9") (pintype "passive"))
    )
    (net (code "26") (name "Net-(JP5-Pad1)") (class "Default")
      (node (ref "JP5") (pin "1") (pinfunction "1_1") (pintype "passive"))
      (node (ref "JP5") (pin "2") (pinfunction "2_2") (pintype "passive"))
      (node (ref "JP5") (pin "3") (pinfunction "3_3") (pintype "passive"))
      (node (ref "JP6") (pin "1") (pinfunction "1_1") (pintype "passive"))
      (node (ref "JP6") (pin "2") (pinfunction "2_2") (pintype "passive"))
      (node (ref "JP6") (pin "3") (pinfunction "3_3") (pintype "passive"))
    )
    (net (code "27") (name "Net-(JP12-1)") (class "Default")
      (node (ref "JP1") (pin "1") (pinfunction "1_1") (pintype "passive"))
      (node (ref "JP12") (pin "P$1") (pinfunction "1_P$1") (pintype "passive"))
    )
    (net (code "28") (name "Net-(JP13-1)") (class "Default")
      (node (ref "JP13") (pin "P$1") (pinfunction "1_P$1") (pintype "passive"))
      (node (ref "JP7") (pin "1") (pinfunction "1_1") (pintype "passive"))
    )
    (net (code "29") (name "Net-(JP14-1)") (class "Default")
      (node (ref "JP14") (pin "P$1") (pinfunction "1_P$1") (pintype "passive"))
      (node (ref "JP8") (pin "1") (pinfunction "1_1") (pintype "passive"))
    )
    (net (code "30") (name "Net-(JP15-1)") (class "Default")
      (node (ref "JP15") (pin "P$1") (pinfunction "1_P$1") (pintype "passive"))
      (node (ref "JP9") (pin "1") (pinfunction "1_1") (pintype "passive"))
    )
    (net (code "31") (name "Net-(JP16-1)") (class "Default")
      (node (ref "JP10") (pin "1") (pinfunction "1_1") (pintype "passive"))
      (node (ref "JP16") (pin "P$1") (pinfunction "1_P$1") (pintype "passive"))
    )
    (net (code "32") (name "Net-(X1-ADC)") (class "Default")
      (node (ref "J22") (pin "1") (pinfunction "1_1") (pintype "passive"))
      (node (ref "J22") (pin "2") (pinfunction "2_2") (pintype "passive"))
      (node (ref "J22") (pin "3") (pinfunction "3_3") (pintype "passive"))
      (node (ref "J22") (pin "4") (pinfunction "4_4") (pintype "passive"))
      (node (ref "J22") (pin "5") (pinfunction "5_5") (pintype "passive"))
      (node (ref "X1") (pin "2") (pinfunction "ADC_2") (pintype "passive"))
    )
    (net (code "33") (name "Net-(X1-CH_PD)") (class "Default")
      (node (ref "J23") (pin "1") (pinfunction "1_1") (pintype "passive"))
      (node (ref "J23") (pin "2") (pinfunction "2_2") (pintype "passive"))
      (node (ref "J23") (pin "3") (pinfunction "3_3") (pintype "passive"))
      (node (ref "J23") (pin "4") (pinfunction "4_4") (pintype "passive"))
      (node (ref "J23") (pin "5") (pinfunction "5_5") (pintype "passive"))
      (node (ref "X1") (pin "3") (pinfunction "CH_PD_3") (pintype "input"))
    )
    (net (code "34") (name "Net-(X1-GPIO0)") (class "Default")
      (node (ref "J3") (pin "1") (pinfunction "1_1") (pintype "passive"))
      (node (ref "J3") (pin "2") (pinfunction "2_2") (pintype "passive"))
      (node (ref "J3") (pin "3") (pinfunction "3_3") (pintype "passive"))
      (node (ref "J3") (pin "4") (pinfunction "4_4") (pintype "passive"))
      (node (ref "J3") (pin "5") (pinfunction "5_5") (pintype "passive"))
      (node (ref "X1") (pin "12") (pinfunction "GPIO0_12") (pintype "bidirectional"))
    )
    (net (code "35") (name "Net-(X1-GPIO2)") (class "Default")
      (node (ref "J4") (pin "1") (pinfunction "1_1") (pintype "passive"))
      (node (ref "J4") (pin "2") (pinfunction "2_2") (pintype "passive"))
      (node (ref "J4") (pin "3") (pinfunction "3_3") (pintype "passive"))
      (node (ref "J4") (pin "4") (pinfunction "4_4") (pintype "passive"))
      (node (ref "J4") (pin "5") (pinfunction "5_5") (pintype "passive"))
      (node (ref "X1") (pin "11") (pinfunction "GPIO2_11") (pintype "bidirectional"))
    )
    (net (code "36") (name "Net-(X1-GPIO4)") (class "Default")
      (node (ref "J2") (pin "1") (pinfunction "1_1") (pintype "passive"))
      (node (ref "J2") (pin "2") (pinfunction "2_2") (pintype "passive"))
      (node (ref "J2") (pin "3") (pinfunction "3_3") (pintype "passive"))
      (node (ref "J2") (pin "4") (pinfunction "4_4") (pintype "passive"))
      (node (ref "J2") (pin "5") (pinfunction "5_5") (pintype "passive"))
      (node (ref "X1") (pin "13") (pinfunction "GPIO4_13") (pintype "bidirectional"))
    )
    (net (code "37") (name "Net-(X1-GPIO5)") (class "Default")
      (node (ref "J39") (pin "1") (pinfunction "1_1") (pintype "passive"))
      (node (ref "J39") (pin "2") (pinfunction "2_2") (pintype "passive"))
      (node (ref "J39") (pin "3") (pinfunction "3_3") (pintype "passive"))
      (node (ref "J39") (pin "4") (pinfunction "4_4") (pintype "passive"))
      (node (ref "J39") (pin "5") (pinfunction "5_5") (pintype "passive"))
      (node (ref "X1") (pin "14") (pinfunction "GPIO5_14") (pintype "bidirectional"))
    )
    (net (code "38") (name "Net-(X1-GPIO12)") (class "Default")
      (node (ref "J26") (pin "1") (pinfunction "1_1") (pintype "passive"))
      (node (ref "J26") (pin "2") (pinfunction "2_2") (pintype "passive"))
      (node (ref "J26") (pin "3") (pinfunction "3_3") (pintype "passive"))
      (node (ref "J26") (pin "4") (pinfunction "4_4") (pintype "passive"))
      (node (ref "J26") (pin "5") (pinfunction "5_5") (pintype "passive"))
      (node (ref "X1") (pin "6") (pinfunction "GPIO12_6") (pintype "bidirectional"))
    )
    (net (code "39") (name "Net-(X1-GPIO13)") (class "Default")
      (node (ref "J27") (pin "1") (pinfunction "1_1") (pintype "passive"))
      (node (ref "J27") (pin "2") (pinfunction "2_2") (pintype "passive"))
      (node (ref "J27") (pin "3") (pinfunction "3_3") (pintype "passive"))
      (node (ref "J27") (pin "4") (pinfunction "4_4") (pintype "passive"))
      (node (ref "J27") (pin "5") (pinfunction "5_5") (pintype "passive"))
      (node (ref "X1") (pin "7") (pinfunction "GPIO13_7") (pintype "bidirectional"))
    )
    (net (code "40") (name "Net-(X1-GPIO14)") (class "Default")
      (node (ref "J25") (pin "1") (pinfunction "1_1") (pintype "passive"))
      (node (ref "J25") (pin "2") (pinfunction "2_2") (pintype "passive"))
      (node (ref "J25") (pin "3") (pinfunction "3_3") (pintype "passive"))
      (node (ref "J25") (pin "4") (pinfunction "4_4") (pintype "passive"))
      (node (ref "J25") (pin "5") (pinfunction "5_5") (pintype "passive"))
      (node (ref "X1") (pin "5") (pinfunction "GPIO14_5") (pintype "bidirectional"))
    )
    (net (code "41") (name "Net-(X1-GPIO15)") (class "Default")
      (node (ref "J5") (pin "1") (pinfunction "1_1") (pintype "passive"))
      (node (ref "J5") (pin "2") (pinfunction "2_2") (pintype "passive"))
      (node (ref "J5") (pin "3") (pinfunction "3_3") (pintype "passive"))
      (node (ref "J5") (pin "4") (pinfunction "4_4") (pintype "passive"))
      (node (ref "J5") (pin "5") (pinfunction "5_5") (pintype "passive"))
      (node (ref "X1") (pin "10") (pinfunction "GPIO15_10") (pintype "bidirectional"))
    )
    (net (code "42") (name "Net-(X1-GPIO16)") (class "Default")
      (node (ref "J24") (pin "1") (pinfunction "1_1") (pintype "passive"))
      (node (ref "J24") (pin "2") (pinfunction "2_2") (pintype "passive"))
      (node (ref "J24") (pin "3") (pinfunction "3_3") (pintype "passive"))
      (node (ref "J24") (pin "4") (pinfunction "4_4") (pintype "passive"))
      (node (ref "J24") (pin "5") (pinfunction "5_5") (pintype "passive"))
      (node (ref "X1") (pin "4") (pinfunction "GPIO16_4") (pintype "bidirectional"))
    )
    (net (code "43") (name "Net-(X1-RESET)") (class "Default")
      (node (ref "J6") (pin "1") (pinfunction "1_1") (pintype "passive"))
      (node (ref "J6") (pin "2") (pinfunction "2_2") (pintype "passive"))
      (node (ref "J6") (pin "3") (pinfunction "3_3") (pintype "passive"))
      (node (ref "J6") (pin "4") (pinfunction "4_4") (pintype "passive"))
      (node (ref "J6") (pin "5") (pinfunction "5_5") (pintype "passive"))
      (node (ref "X1") (pin "1") (pinfunction "RESET_1") (pintype "input"))
    )
    (net (code "44") (name "Net-(X1-RXD)") (class "Default")
      (node (ref "J7") (pin "1") (pinfunction "1_1") (pintype "passive"))
      (node (ref "J7") (pin "2") (pinfunction "2_2") (pintype "passive"))
      (node (ref "J7") (pin "3") (pinfunction "3_3") (pintype "passive"))
      (node (ref "J7") (pin "4") (pinfunction "4_4") (pintype "passive"))
      (node (ref "J7") (pin "5") (pinfunction "5_5") (pintype "passive"))
      (node (ref "RX") (pin "1") (pinfunction "1_1") (pintype "passive"))
      (node (ref "X1") (pin "15") (pinfunction "RXD_15") (pintype "input"))
    )
    (net (code "45") (name "Net-(X1-TXD)") (class "Default")
      (node (ref "J8") (pin "1") (pinfunction "1_1") (pintype "passive"))
      (node (ref "J8") (pin "2") (pinfunction "2_2") (pintype "passive"))
      (node (ref "J8") (pin "3") (pinfunction "3_3") (pintype "passive"))
      (node (ref "J8") (pin "4") (pinfunction "4_4") (pintype "passive"))
      (node (ref "J8") (pin "5") (pinfunction "5_5") (pintype "passive"))
      (node (ref "TX") (pin "1") (pinfunction "1_1") (pintype "passive"))
      (node (ref "X1") (pin "16") (pinfunction "TXD_16") (pintype "output"))
    )
    (net (code "46") (name "Net-(X2-GND-PadBASE@1)") (class "Default")
      (node (ref "X2") (pin "BASE@1") (pinfunction "GND_BASE@1") (pintype "power_in"))
      (node (ref "X2") (pin "BASE@2") (pinfunction "GND_BASE@2") (pintype "power_in"))
      (node (ref "X2") (pin "GND") (pinfunction "GND_GND") (pintype "power_in"))
      (node (ref "X2") (pin "SPRT@1") (pinfunction "GND_SPRT@1") (pintype "power_in"))
      (node (ref "X2") (pin "SPRT@2") (pinfunction "GND_SPRT@2") (pintype "power_in"))
      (node (ref "X2") (pin "SPRT@3") (pinfunction "GND_SPRT@3") (pintype "power_in"))
      (node (ref "X2") (pin "SPRT@4") (pinfunction "GND_SPRT@4") (pintype "power_in"))
    )
    (net (code "47") (name "VCC") (class "Default")
      (node (ref "DC") (pin "1") (pinfunction "VIN_1") (pintype "passive"))
      (node (ref "U2") (pin "1") (pinfunction "IN_1") (pintype "input"))
      (node (ref "U2") (pin "3") (pinfunction "EN_3") (pintype "input"))
      (node (ref "X2") (pin "VBUS") (pinfunction "VBUS_VBUS") (pintype "power_in"))
    )
    (net (code "48") (name "VDD") (class "Default")
      (node (ref "DC") (pin "3") (pinfunction "VOUT_3") (pintype "passive"))
      (node (ref "PAD15") (pin "1") (pinfunction "P_1") (pintype "passive"))
      (node (ref "PAD25") (pin "1") (pinfunction "P_1") (pintype "passive"))
      (node (ref "PAD26") (pin "1") (pinfunction "P_1") (pintype "passive"))
      (node (ref "PAD27") (pin "1") (pinfunction "P_1") (pintype "passive"))
      (node (ref "PAD28") (pin "1") (pinfunction "P_1") (pintype "passive"))
      (node (ref "PAD29") (pin "1") (pinfunction "P_1") (pintype "passive"))
      (node (ref "PAD30") (pin "1") (pinfunction "P_1") (pintype "passive"))
      (node (ref "PAD31") (pin "1") (pinfunction "P_1") (pintype "passive"))
      (node (ref "PAD32") (pin "1") (pinfunction "P_1") (pintype "passive"))
      (node (ref "PAD33") (pin "1") (pinfunction "P_1") (pintype "passive"))
      (node (ref "PAD34") (pin "1") (pinfunction "P_1") (pintype "passive"))
      (node (ref "PAD35") (pin "1") (pinfunction "P_1") (pintype "passive"))
      (node (ref "PAD36") (pin "1") (pinfunction "P_1") (pintype "passive"))
      (node (ref "PAD37") (pin "1") (pinfunction "P_1") (pintype "passive"))
      (node (ref "PAD39") (pin "1") (pinfunction "P_1") (pintype "passive"))
      (node (ref "PAD40") (pin "1") (pinfunction "P_1") (pintype "passive"))
      (node (ref "PAD41") (pin "1") (pinfunction "P_1") (pintype "passive"))
      (node (ref "PAD43") (pin "1") (pinfunction "P_1") (pintype "passive"))
      (node (ref "PAD44") (pin "1") (pinfunction "P_1") (pintype "passive"))
      (node (ref "PAD442") (pin "1") (pinfunction "P_1") (pintype "passive"))
      (node (ref "PAD443") (pin "1") (pinfunction "P_1") (pintype "passive"))
      (node (ref "PAD444") (pin "1") (pinfunction "P_1") (pintype "passive"))
      (node (ref "PAD445") (pin "1") (pinfunction "P_1") (pintype "passive"))
      (node (ref "PAD446") (pin "1") (pinfunction "P_1") (pintype "passive"))
      (node (ref "PAD447") (pin "1") (pinfunction "P_1") (pintype "passive"))
      (node (ref "PAD448") (pin "1") (pinfunction "P_1") (pintype "passive"))
      (node (ref "PAD449") (pin "1") (pinfunction "P_1") (pintype "passive"))
      (node (ref "PAD45") (pin "1") (pinfunction "P_1") (pintype "passive"))
      (node (ref "PAD450") (pin "1") (pinfunction "P_1") (pintype "passive"))
      (node (ref "PAD451") (pin "1") (pinfunction "P_1") (pintype "passive"))
      (node (ref "PAD452") (pin "1") (pinfunction "P_1") (pintype "passive"))
      (node (ref "PAD453") (pin "1") (pinfunction "P_1") (pintype "passive"))
      (node (ref "PAD454") (pin "1") (pinfunction "P_1") (pintype "passive"))
      (node (ref "PAD455") (pin "1") (pinfunction "P_1") (pintype "passive"))
      (node (ref "PAD456") (pin "1") (pinfunction "P_1") (pintype "passive"))
      (node (ref "PAD457") (pin "1") (pinfunction "P_1") (pintype "passive"))
      (node (ref "PAD458") (pin "1") (pinfunction "P_1") (pintype "passive"))
      (node (ref "PAD459") (pin "1") (pinfunction "P_1") (pintype "passive"))
      (node (ref "PAD46") (pin "1") (pinfunction "P_1") (pintype "passive"))
      (node (ref "PAD460") (pin "1") (pinfunction "P_1") (pintype "passive"))
      (node (ref "PAD461") (pin "1") (pinfunction "P_1") (pintype "passive"))
      (node (ref "PAD462") (pin "1") (pinfunction "P_1") (pintype "passive"))
      (node (ref "U2") (pin "5") (pinfunction "OUT_5") (pintype "passive"))
      (node (ref "X1") (pin "8") (pinfunction "VCC_8") (pintype "power_in"))
    )
    (net (code "49") (name "unconnected-(U2-BP-Pad4)") (class "Default")
      (node (ref "U2") (pin "4") (pinfunction "BP_4") (pintype "input"))
    )
    (net (code "50") (name "unconnected-(X1-CLK-Pad20)") (class "Default")
      (node (ref "X1") (pin "20") (pinfunction "CLK_20") (pintype "bidirectional"))
    )
    (net (code "51") (name "unconnected-(X1-CS-Pad17)") (class "Default")
      (node (ref "X1") (pin "17") (pinfunction "CS_17") (pintype "bidirectional"))
    )
    (net (code "52") (name "unconnected-(X1-DI-Pad21)") (class "Default")
      (node (ref "X1") (pin "21") (pinfunction "DI_21") (pintype "bidirectional"))
    )
    (net (code "53") (name "unconnected-(X1-DO-Pad18)") (class "Default")
      (node (ref "X1") (pin "18") (pinfunction "DO_18") (pintype "bidirectional"))
    )
    (net (code "54") (name "unconnected-(X1-GPIO9-Pad22)") (class "Default")
      (node (ref "X1") (pin "22") (pinfunction "GPIO9_22") (pintype "bidirectional"))
    )
    (net (code "55") (name "unconnected-(X1-GPIO10-Pad19)") (class "Default")
      (node (ref "X1") (pin "19") (pinfunction "GPIO10_19") (pintype "bidirectional"))
    )
    (net (code "56") (name "unconnected-(X2-PadD+)") (class "Default")
      (node (ref "X2") (pin "D+") (pinfunction "D+_D+") (pintype "bidirectional"))
    )
    (net (code "57") (name "unconnected-(X2-PadD-)") (class "Default")
      (node (ref "X2") (pin "D-") (pinfunction "D-_D-") (pintype "bidirectional"))
    )
    (net (code "58") (name "unconnected-(X2-PadID)") (class "Default")
      (node (ref "X2") (pin "ID") (pinfunction "ID_ID") (pintype "bidirectional"))
    )
  )
)
